# blink1mk3_005t6_5050_4l.net
KiCad netlist of a schematic drawn in EAGLE
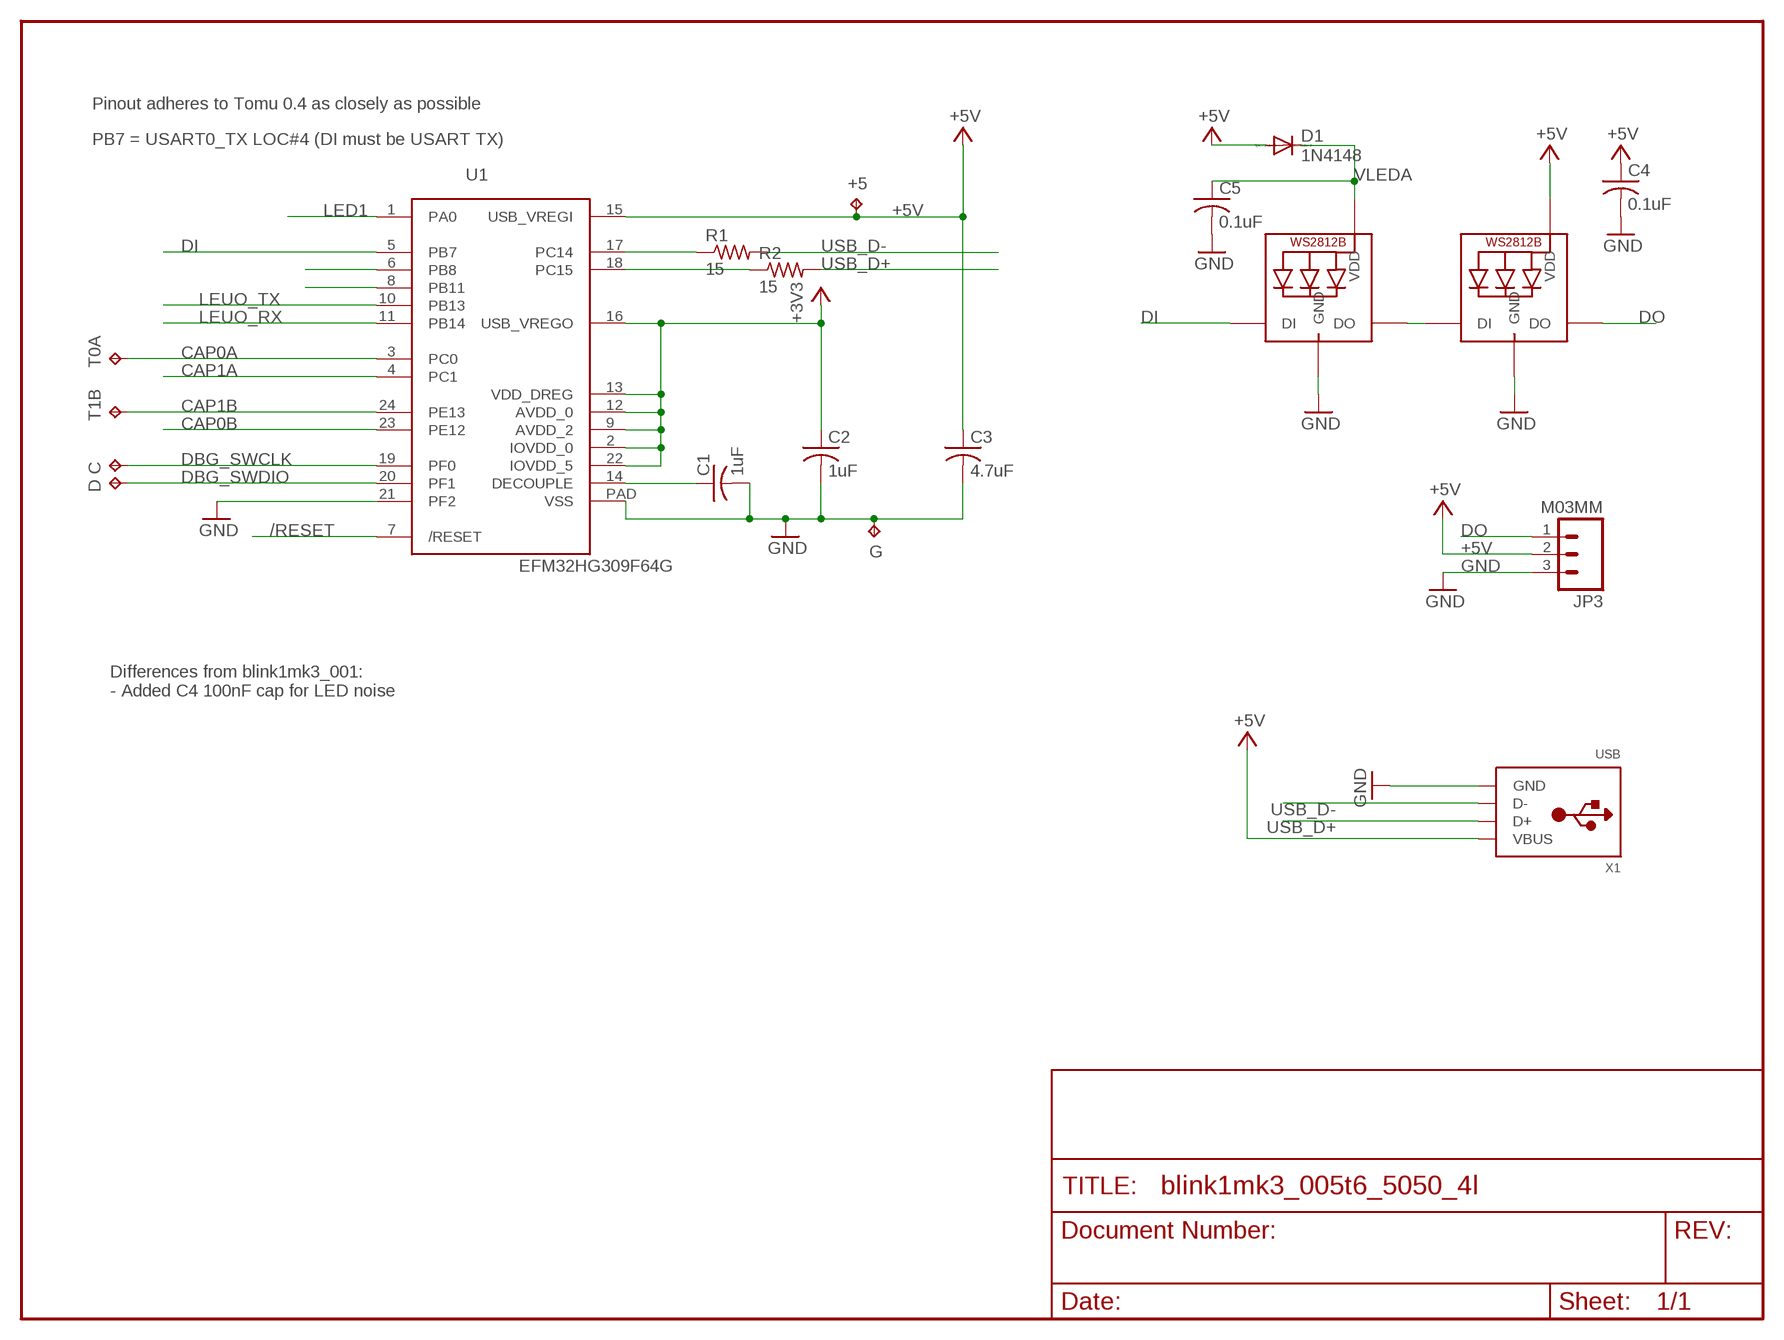
[diagram p0: schematic, sheet 1]

(export (version "E")
  (design (tool "Eeschema 10.0.6"))
  (components
    (comp (ref "+5")
      (value "TPTP10R")
      (footprint "eagle-import:TP10R")
      (libsource (lib "eagle-import") (part "TPTP10R"))
    )
    (comp (ref "C")
      (value "TPTP10R")
      (footprint "eagle-import:TP10R")
      (libsource (lib "eagle-import") (part "TPTP10R"))
    )
    (comp (ref "C1")
      (value "1uF")
      (footprint "eagle-import:C0402")
      (libsource (lib "eagle-import") (part "C-USC0402"))
    )
    (comp (ref "C2")
      (value "1uF")
      (footprint "eagle-import:C0402")
      (libsource (lib "eagle-import") (part "C-USC0402"))
    )
    (comp (ref "C3")
      (value "4.7uF")
      (footprint "eagle-import:C0402")
      (libsource (lib "eagle-import") (part "C-USC0402"))
    )
    (comp (ref "C4")
      (value "0.1uF")
      (footprint "eagle-import:C0402")
      (libsource (lib "eagle-import") (part "C-USC0402"))
    )
    (comp (ref "C5")
      (value "0.1uF")
      (footprint "eagle-import:C0402")
      (libsource (lib "eagle-import") (part "C-USC0402"))
    )
    (comp (ref "D")
      (value "TPTP10R")
      (footprint "eagle-import:TP10R")
      (libsource (lib "eagle-import") (part "TPTP10R"))
    )
    (comp (ref "D1")
      (value "1N4148")
      (footprint "eagle-import:SOD523")
      (libsource (lib "eagle-import") (part "DIODE-SOD523"))
    )
    (comp (ref "G")
      (value "TPTP10R")
      (footprint "eagle-import:TP10R")
      (libsource (lib "eagle-import") (part "TPTP10R"))
    )
    (comp (ref "JP3")
      (value "M03MM")
      (footprint "eagle-import:1X03-1.5MM")
      (libsource (lib "eagle-import") (part "M03MM"))
    )
    (comp (ref "LED1")
      (value "SK6812MINI")
      (footprint "eagle-import:WS2812B")
      (libsource (lib "eagle-import") (part "WS2812B5050"))
    )
    (comp (ref "LED2")
      (value "SK6812MINI")
      (footprint "eagle-import:WS2812B")
      (libsource (lib "eagle-import") (part "WS2812B5050"))
    )
    (comp (ref "R1")
      (value "15")
      (footprint "eagle-import:R0402")
      (libsource (lib "eagle-import") (part "R-US_R0402"))
    )
    (comp (ref "R2")
      (value "15")
      (footprint "eagle-import:R0402")
      (libsource (lib "eagle-import") (part "R-US_R0402"))
    )
    (comp (ref "T0A")
      (value "TPTP15R")
      (footprint "eagle-import:TP15R")
      (libsource (lib "eagle-import") (part "TPTP15R"))
    )
    (comp (ref "T1B")
      (value "TPTP15R")
      (footprint "eagle-import:TP15R")
      (libsource (lib "eagle-import") (part "TPTP15R"))
    )
    (comp (ref "U1")
      (value "EFM32HG309F64G")
      (footprint "eagle-import:QFN24PAD")
      (libsource (lib "eagle-import") (part "EFM32HG309F64G"))
    )
    (comp (ref "X1")
      (value "USB")
      (footprint "eagle-import:MOLEX-48037-1000")
      (libsource (lib "eagle-import") (part "USB"))
    )
  )
  (nets
    (net (code "1") (name "+3V3") (class "Default")
      (node (ref "C2") (pin "1") (pinfunction "1_1") (pintype "passive"))
      (node (ref "U1") (pin "12") (pinfunction "AVDD_0_12") (pintype "bidirectional"))
      (node (ref "U1") (pin "13") (pinfunction "VDD_DREG_13") (pintype "bidirectional"))
      (node (ref "U1") (pin "16") (pinfunction "USB_VREGO_16") (pintype "bidirectional"))
      (node (ref "U1") (pin "2") (pinfunction "IOVDD_0_2") (pintype "bidirectional"))
      (node (ref "U1") (pin "22") (pinfunction "IOVDD_5_22") (pintype "bidirectional"))
      (node (ref "U1") (pin "9") (pinfunction "AVDD_2_9") (pintype "bidirectional"))
    )
    (net (code "2") (name "+5V") (class "Default")
      (node (ref "+5") (pin "TP") (pinfunction "TP_TP") (pintype "input"))
      (node (ref "C3") (pin "1") (pinfunction "1_1") (pintype "passive"))
      (node (ref "C4") (pin "1") (pinfunction "1_1") (pintype "passive"))
      (node (ref "D1") (pin "A") (pinfunction "A_A") (pintype "passive"))
      (node (ref "JP3") (pin "2") (pinfunction "2_2") (pintype "passive"))
      (node (ref "LED2") (pin "1-VDD") (pinfunction "VDD_1-VDD") (pintype "power_in"))
      (node (ref "U1") (pin "15") (pinfunction "USB_VREGI_15") (pintype "bidirectional"))
      (node (ref "X1") (pin "1") (pinfunction "VBUS_1") (pintype "power_in"))
    )
    (net (code "3") (name "/CAP0A") (class "Default")
      (node (ref "T0A") (pin "TP") (pinfunction "TP_TP") (pintype "input"))
      (node (ref "U1") (pin "3") (pinfunction "PC0_3") (pintype "bidirectional"))
    )
    (net (code "4") (name "/CAP0B") (class "Default")
      (node (ref "U1") (pin "23") (pinfunction "PE12_23") (pintype "bidirectional"))
    )
    (net (code "5") (name "/CAP1A") (class "Default")
      (node (ref "U1") (pin "4") (pinfunction "PC1_4") (pintype "bidirectional"))
    )
    (net (code "6") (name "/CAP1B") (class "Default")
      (node (ref "T1B") (pin "TP") (pinfunction "TP_TP") (pintype "input"))
      (node (ref "U1") (pin "24") (pinfunction "PE13_24") (pintype "bidirectional"))
    )
    (net (code "7") (name "/DBG_SWCLK") (class "Default")
      (node (ref "C") (pin "TP") (pinfunction "TP_TP") (pintype "input"))
      (node (ref "U1") (pin "19") (pinfunction "PF0_19") (pintype "bidirectional"))
    )
    (net (code "8") (name "/DBG_SWDIO") (class "Default")
      (node (ref "D") (pin "TP") (pinfunction "TP_TP") (pintype "input"))
      (node (ref "U1") (pin "20") (pinfunction "PF1_20") (pintype "bidirectional"))
    )
    (net (code "9") (name "/DI") (class "Default")
      (node (ref "LED1") (pin "4-DIN") (pinfunction "DI_4-DIN") (pintype "input"))
      (node (ref "U1") (pin "5") (pinfunction "PB7_5") (pintype "bidirectional"))
    )
    (net (code "10") (name "/DO") (class "Default")
      (node (ref "JP3") (pin "1") (pinfunction "1_1") (pintype "passive"))
      (node (ref "LED2") (pin "2-DOUT") (pinfunction "DO_2-DOUT") (pintype "output"))
    )
    (net (code "11") (name "/LED1") (class "Default")
      (node (ref "U1") (pin "1") (pinfunction "PA0_1") (pintype "bidirectional"))
    )
    (net (code "12") (name "/LEUO_RX") (class "Default")
      (node (ref "U1") (pin "11") (pinfunction "PB14_11") (pintype "bidirectional"))
    )
    (net (code "13") (name "/LEUO_TX") (class "Default")
      (node (ref "U1") (pin "10") (pinfunction "PB13_10") (pintype "bidirectional"))
    )
    (net (code "14") (name "/USB_D+") (class "Default")
      (node (ref "R2") (pin "2") (pinfunction "2_2") (pintype "passive"))
      (node (ref "X1") (pin "3") (pinfunction "D+_3") (pintype "bidirectional"))
    )
    (net (code "15") (name "/USB_D-") (class "Default")
      (node (ref "R1") (pin "2") (pinfunction "2_2") (pintype "passive"))
      (node (ref "X1") (pin "2") (pinfunction "D-_2") (pintype "bidirectional"))
    )
    (net (code "16") (name "/VLEDA") (class "Default")
      (node (ref "C5") (pin "1") (pinfunction "1_1") (pintype "passive"))
      (node (ref "D1") (pin "C") (pinfunction "C_C") (pintype "passive"))
      (node (ref "LED1") (pin "1-VDD") (pinfunction "VDD_1-VDD") (pintype "power_in"))
    )
    (net (code "17") (name "/{slash}RESET") (class "Default")
      (node (ref "U1") (pin "7") (pinfunction "/RESET_7") (pintype "bidirectional"))
    )
    (net (code "18") (name "GND") (class "Default")
      (node (ref "C1") (pin "2") (pinfunction "2_2") (pintype "passive"))
      (node (ref "C2") (pin "2") (pinfunction "2_2") (pintype "passive"))
      (node (ref "C3") (pin "2") (pinfunction "2_2") (pintype "passive"))
      (node (ref "C4") (pin "2") (pinfunction "2_2") (pintype "passive"))
      (node (ref "C5") (pin "2") (pinfunction "2_2") (pintype "passive"))
      (node (ref "G") (pin "TP") (pinfunction "TP_TP") (pintype "input"))
      (node (ref "JP3") (pin "3") (pinfunction "3_3") (pintype "passive"))
      (node (ref "LED1") (pin "3-GND") (pinfunction "GND_3-GND") (pintype "power_in"))
      (node (ref "LED2") (pin "3-GND") (pinfunction "GND_3-GND") (pintype "power_in"))
      (node (ref "U1") (pin "21") (pinfunction "PF2_21") (pintype "bidirectional"))
      (node (ref "U1") (pin "PAD") (pinfunction "VSS_PAD") (pintype "bidirectional"))
      (node (ref "X1") (pin "4") (pinfunction "GND_4") (pintype "power_in"))
    )
    (net (code "19") (name "Net-(LED1-DO)") (class "Default")
      (node (ref "LED1") (pin "2-DOUT") (pinfunction "DO_2-DOUT") (pintype "output"))
      (node (ref "LED2") (pin "4-DIN") (pinfunction "DI_4-DIN") (pintype "input"))
    )
    (net (code "20") (name "Net-(U1-DECOUPLE)") (class "Default")
      (node (ref "C1") (pin "1") (pinfunction "1_1") (pintype "passive"))
      (node (ref "U1") (pin "14") (pinfunction "DECOUPLE_14") (pintype "bidirectional"))
    )
    (net (code "21") (name "Net-(U1-PC14)") (class "Default")
      (node (ref "R1") (pin "1") (pinfunction "1_1") (pintype "passive"))
      (node (ref "U1") (pin "17") (pinfunction "PC14_17") (pintype "bidirectional"))
    )
    (net (code "22") (name "Net-(U1-PC15)") (class "Default")
      (node (ref "R2") (pin "1") (pinfunction "1_1") (pintype "passive"))
      (node (ref "U1") (pin "18") (pinfunction "PC15_18") (pintype "bidirectional"))
    )
    (net (code "23") (name "unconnected-(U1-PB8-Pad6)") (class "Default")
      (node (ref "U1") (pin "6") (pinfunction "PB8_6") (pintype "bidirectional"))
    )
    (net (code "24") (name "unconnected-(U1-PB11-Pad8)") (class "Default")
      (node (ref "U1") (pin "8") (pinfunction "PB11_8") (pintype "bidirectional"))
    )
  )
)
